# LED.net
KiCad netlist of a schematic drawn in EAGLE
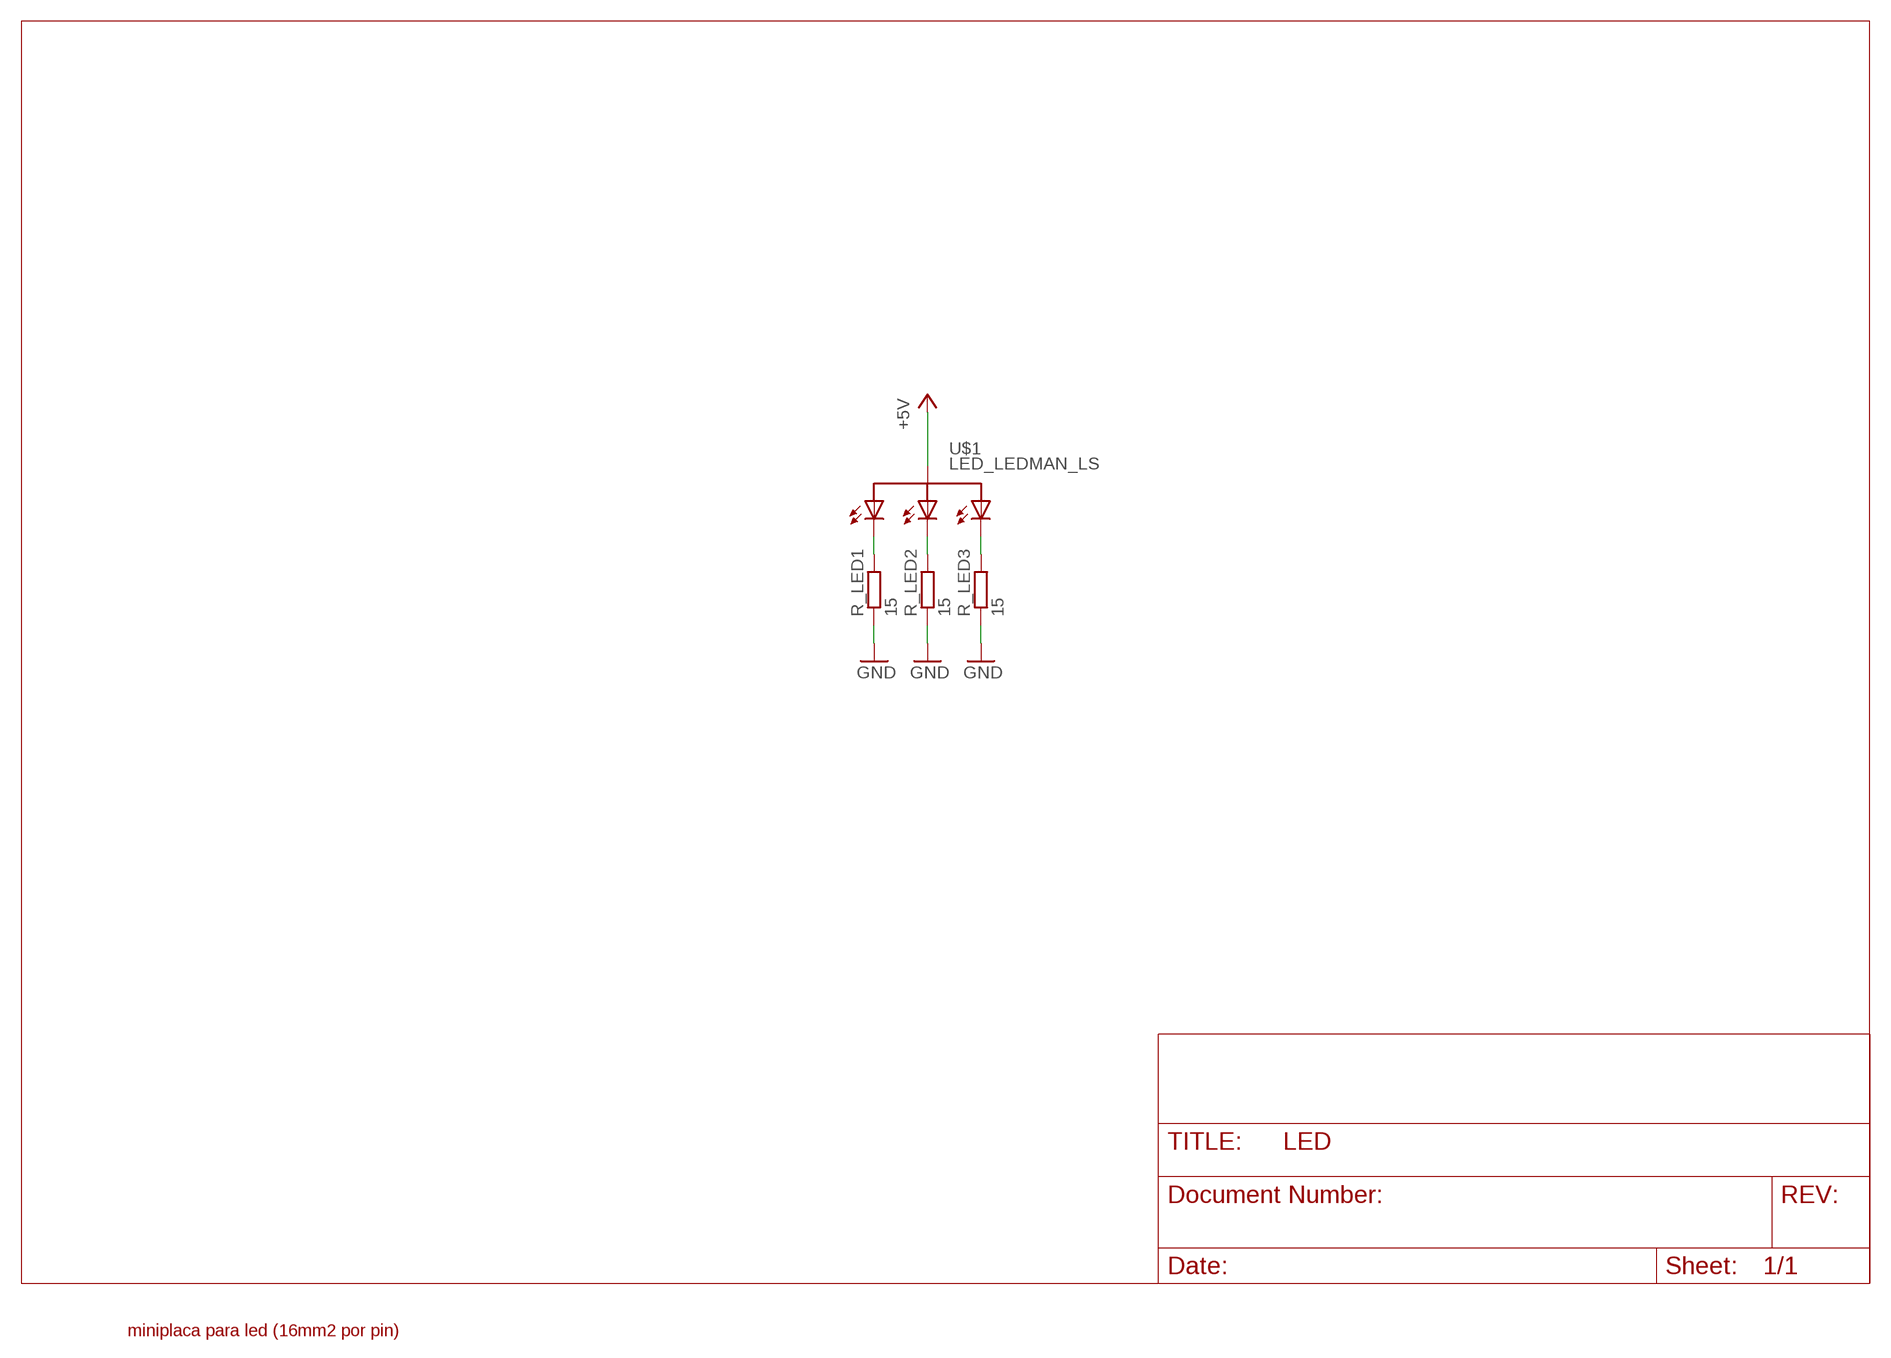
[diagram p0: schematic, sheet 1]

(export (version "E")
  (design (tool "Eeschema 10.0.6"))
  (components
    (comp (ref "R_LED1")
      (value "15")
      (footprint "eagle-import:R1206")
      (libsource (lib "eagle-import") (part "R-EU_R1206"))
    )
    (comp (ref "R_LED2")
      (value "15")
      (footprint "eagle-import:R1206")
      (libsource (lib "eagle-import") (part "R-EU_R1206"))
    )
    (comp (ref "R_LED3")
      (value "15")
      (footprint "eagle-import:R1206")
      (libsource (lib "eagle-import") (part "R-EU_R1206"))
    )
    (comp (ref "U$1")
      (value "LED_LEDMAN_LS")
      (footprint "eagle-import:LED_LEDMAN_LS")
      (libsource (lib "eagle-import") (part "LED_LEDMAN_LS"))
    )
  )
  (nets
    (net (code "1") (name "+5V") (class "Default")
      (node (ref "U$1") (pin "2") (pinfunction "ANODO_2") (pintype "passive"))
    )
    (net (code "2") (name "GND") (class "Default")
      (node (ref "R_LED1") (pin "1") (pinfunction "1_1") (pintype "passive"))
      (node (ref "R_LED2") (pin "1") (pinfunction "1_1") (pintype "passive"))
      (node (ref "R_LED3") (pin "1") (pinfunction "1_1") (pintype "passive"))
    )
    (net (code "3") (name "Net-(U$1-C1)") (class "Default")
      (node (ref "R_LED1") (pin "2") (pinfunction "2_2") (pintype "passive"))
      (node (ref "U$1") (pin "1") (pinfunction "C1_1") (pintype "passive"))
    )
    (net (code "4") (name "Net-(U$1-C2)") (class "Default")
      (node (ref "R_LED2") (pin "2") (pinfunction "2_2") (pintype "passive"))
      (node (ref "U$1") (pin "3") (pinfunction "C2_3") (pintype "passive"))
    )
    (net (code "5") (name "Net-(U$1-C3)") (class "Default")
      (node (ref "R_LED3") (pin "2") (pinfunction "2_2") (pintype "passive"))
      (node (ref "U$1") (pin "4") (pinfunction "C3_4") (pintype "passive"))
    )
  )
)
